# Papra_v0_5.net
KiCad netlist of a schematic drawn in EAGLE
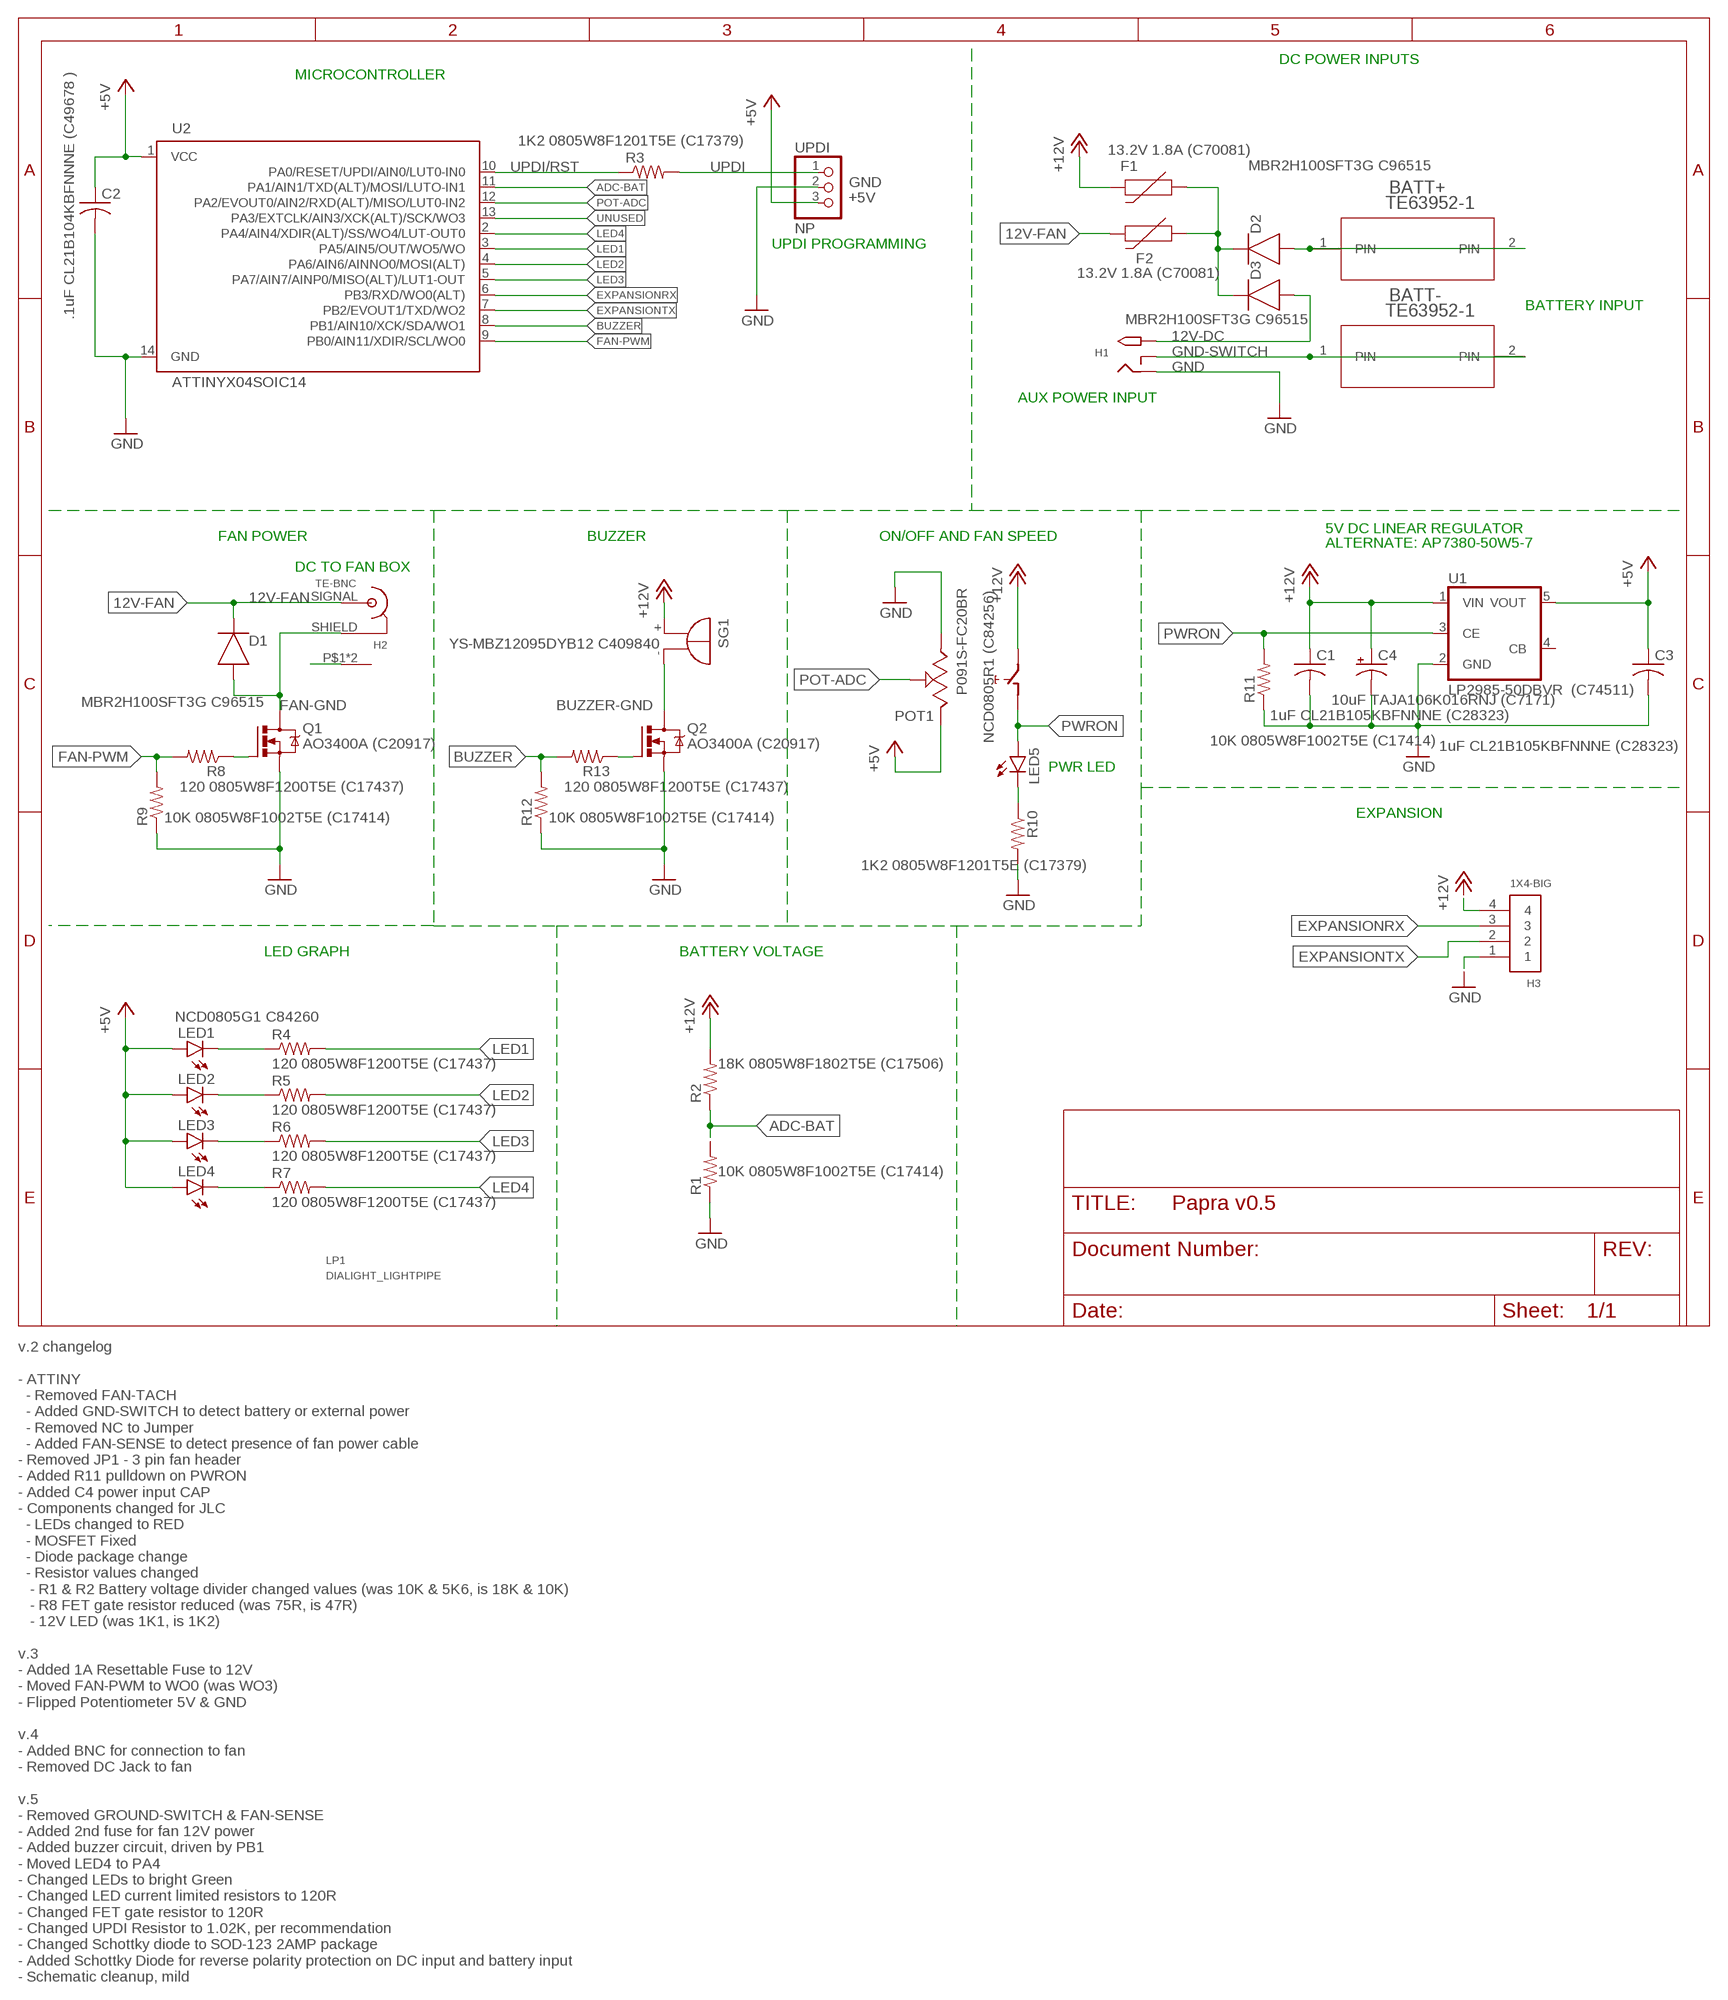
[diagram p0: schematic, sheet 1]

(export (version "E")
  (design (tool "Eeschema 10.0.6"))
  (components
    (comp (ref "BATT+")
      (value "TE63952-1")
      (footprint "eagle-import:TE63952-1")
      (libsource (lib "eagle-import") (part "TE63952-1"))
    )
    (comp (ref "BATT-")
      (value "TE63952-1")
      (footprint "eagle-import:TE63952-1")
      (libsource (lib "eagle-import") (part "TE63952-1"))
    )
    (comp (ref "C1")
      (value "1uF CL21B105KBFNNNE (C28323)")
      (footprint "eagle-import:C0805")
      (libsource (lib "eagle-import") (part "C-USC0805"))
    )
    (comp (ref "C2")
      (value ".1uF CL21B104KBFNNNE (C49678 )")
      (footprint "eagle-import:C0805")
      (libsource (lib "eagle-import") (part "C-USC0805"))
    )
    (comp (ref "C3")
      (value "1uF CL21B105KBFNNNE (C28323)")
      (footprint "eagle-import:C0805")
      (libsource (lib "eagle-import") (part "C-USC0805"))
    )
    (comp (ref "C4")
      (value "10uF TAJA106K016RNJ (C7171)")
      (footprint "eagle-import:A_3216-18R")
      (libsource (lib "eagle-import") (part "CPOL-USA/3216-18R"))
    )
    (comp (ref "D1")
      (value "MBR2H100SFT3G C96515")
      (footprint "eagle-import:SODFL3718X115")
      (libsource (lib "eagle-import") (part "DIODEDO-219-AB(SOD123F)_"))
    )
    (comp (ref "D2")
      (value "MBR2H100SFT3G C96515")
      (footprint "eagle-import:SODFL3718X115")
      (libsource (lib "eagle-import") (part "DIODEDO-219-AB(SOD123F)_"))
    )
    (comp (ref "D3")
      (value "MBR2H100SFT3G C96515")
      (footprint "eagle-import:SODFL3718X115")
      (libsource (lib "eagle-import") (part "DIODEDO-219-AB(SOD123F)_"))
    )
    (comp (ref "F1")
      (value "13.2V 1.8A (C70081)")
      (footprint "eagle-import:1206")
      (libsource (lib "eagle-import") (part "PPTC_HALF-AMP"))
    )
    (comp (ref "F2")
      (value "13.2V 1.8A (C70081)")
      (footprint "eagle-import:1206")
      (libsource (lib "eagle-import") (part "PPTC_HALF-AMP"))
    )
    (comp (ref "H1")
      (value "M-CUI-PJ-066A")
      (footprint "eagle-import:DCJACK-PJ-066A")
      (libsource (lib "eagle-import") (part "PJ-066A"))
    )
    (comp (ref "H2")
      (value "TE-BNC")
      (footprint "eagle-import:TE-BNC")
      (libsource (lib "eagle-import") (part "TE-BNC"))
    )
    (comp (ref "H3")
      (value "1X4-BIG")
      (footprint "eagle-import:1X04-BIG")
      (libsource (lib "eagle-import") (part "1X4-BIG"))
    )
    (comp (ref "LED1")
      (value "NCD0805G1 C84260")
      (footprint "eagle-import:CHIPLED_0805")
      (libsource (lib "eagle-import") (part "LEDCHIPLED_0805"))
    )
    (comp (ref "LED2")
      (value "NCD0805G1 C84260")
      (footprint "eagle-import:CHIPLED_0805")
      (libsource (lib "eagle-import") (part "LEDCHIPLED_0805"))
    )
    (comp (ref "LED3")
      (value "NCD0805G1 C84260")
      (footprint "eagle-import:CHIPLED_0805")
      (libsource (lib "eagle-import") (part "LEDCHIPLED_0805"))
    )
    (comp (ref "LED4")
      (value "NCD0805G1 C84260")
      (footprint "eagle-import:CHIPLED_0805")
      (libsource (lib "eagle-import") (part "LEDCHIPLED_0805"))
    )
    (comp (ref "LED5")
      (value "NCD0805R1 (C84256)")
      (footprint "eagle-import:CHIPLED_0805")
      (libsource (lib "eagle-import") (part "LEDCHIPLED_0805"))
    )
    (comp (ref "LP1")
      (value "DIALIGHT_LIGHTPIPE")
      (footprint "eagle-import:DIALIGHT_5151020F__LEDS")
      (libsource (lib "eagle-import") (part "DIALIGHT_LIGHTPIPE"))
    )
    (comp (ref "POT1")
      (value "P091S-FC20BR")
      (footprint "eagle-import:P091S-FC20BR")
      (libsource (lib "eagle-import") (part "P091S-FC20BR"))
    )
    (comp (ref "Q1")
      (value "AO3400A (C20917)")
      (footprint "eagle-import:SOT23")
      (fields (field (name "MANUFACTURER") "ON Semiconductor") (field (name "MPN") "BSS123L"))
      (libsource (lib "eagle-import") (part "NMOSFET_-SOT23BSS123"))
    )
    (comp (ref "Q2")
      (value "AO3400A (C20917)")
      (footprint "eagle-import:SOT23")
      (fields (field (name "MANUFACTURER") "ON Semiconductor") (field (name "MPN") "BSS123L"))
      (libsource (lib "eagle-import") (part "NMOSFET_-SOT23BSS123"))
    )
    (comp (ref "R1")
      (value "10K 0805W8F1002T5E (C17414)")
      (footprint "eagle-import:R0805")
      (libsource (lib "eagle-import") (part "R-US_R0805"))
    )
    (comp (ref "R2")
      (value "18K 0805W8F1802T5E (C17506)")
      (footprint "eagle-import:R0805")
      (libsource (lib "eagle-import") (part "R-US_R0805"))
    )
    (comp (ref "R3")
      (value "1K2 0805W8F1201T5E (C17379)")
      (footprint "eagle-import:R0805")
      (libsource (lib "eagle-import") (part "R-US_R0805"))
    )
    (comp (ref "R4")
      (value "120 0805W8F1200T5E (C17437)")
      (footprint "eagle-import:R0805")
      (libsource (lib "eagle-import") (part "R-US_R0805"))
    )
    (comp (ref "R5")
      (value "120 0805W8F1200T5E (C17437)")
      (footprint "eagle-import:R0805")
      (libsource (lib "eagle-import") (part "R-US_R0805"))
    )
    (comp (ref "R6")
      (value "120 0805W8F1200T5E (C17437)")
      (footprint "eagle-import:R0805")
      (libsource (lib "eagle-import") (part "R-US_R0805"))
    )
    (comp (ref "R7")
      (value "120 0805W8F1200T5E (C17437)")
      (footprint "eagle-import:R0805")
      (libsource (lib "eagle-import") (part "R-US_R0805"))
    )
    (comp (ref "R8")
      (value "120 0805W8F1200T5E (C17437)")
      (footprint "eagle-import:R0805")
      (libsource (lib "eagle-import") (part "R-US_R0805"))
    )
    (comp (ref "R9")
      (value "10K 0805W8F1002T5E (C17414)")
      (footprint "eagle-import:R0805")
      (libsource (lib "eagle-import") (part "R-US_R0805"))
    )
    (comp (ref "R10")
      (value "1K2 0805W8F1201T5E (C17379)")
      (footprint "eagle-import:R0805")
      (libsource (lib "eagle-import") (part "R-US_R0805"))
    )
    (comp (ref "R11")
      (value "10K 0805W8F1002T5E (C17414)")
      (footprint "eagle-import:R0805")
      (libsource (lib "eagle-import") (part "R-US_R0805"))
    )
    (comp (ref "R12")
      (value "10K 0805W8F1002T5E (C17414)")
      (footprint "eagle-import:R0805")
      (libsource (lib "eagle-import") (part "R-US_R0805"))
    )
    (comp (ref "R13")
      (value "120 0805W8F1200T5E (C17437)")
      (footprint "eagle-import:R0805")
      (libsource (lib "eagle-import") (part "R-US_R0805"))
    )
    (comp (ref "SG1")
      (value "YS-MBZ12095DYB12 C409840")
      (footprint "eagle-import:F_TMB")
      (libsource (lib "eagle-import") (part "F/TMB"))
    )
    (comp (ref "U1")
      (value "LP2985-50DBVR (C74511)")
      (footprint "eagle-import:SOT25")
      (libsource (lib "eagle-import") (part "TS520533"))
    )
    (comp (ref "U2")
      (value "ATTINYX04SOIC14")
      (footprint "eagle-import:SOIC127P600X144-14")
      (libsource (lib "eagle-import") (part "ATTINYX04SOIC14"))
    )
    (comp (ref "UPDI")
      (value "NP")
      (footprint "eagle-import:1X03")
      (libsource (lib "eagle-import") (part "PINHD-1X3"))
    )
  )
  (nets
    (net (code "1") (name "+5V") (class "Default")
      (node (ref "C2") (pin "1") (pinfunction "1_1") (pintype "passive"))
      (node (ref "C3") (pin "1") (pinfunction "1_1") (pintype "passive"))
      (node (ref "LED1") (pin "A") (pinfunction "A_A") (pintype "passive"))
      (node (ref "LED2") (pin "A") (pinfunction "A_A") (pintype "passive"))
      (node (ref "LED3") (pin "A") (pinfunction "A_A") (pintype "passive"))
      (node (ref "LED4") (pin "A") (pinfunction "A_A") (pintype "passive"))
      (node (ref "POT1") (pin "3") (pinfunction "3_3") (pintype "passive"))
      (node (ref "U1") (pin "5") (pinfunction "VOUT_5") (pintype "passive"))
      (node (ref "U2") (pin "1") (pinfunction "VCC_1") (pintype "power_in"))
      (node (ref "UPDI") (pin "3") (pinfunction "3_3") (pintype "passive"))
    )
    (net (code "2") (name "+12V") (class "Default")
      (node (ref "C1") (pin "1") (pinfunction "1_1") (pintype "passive"))
      (node (ref "C4") (pin "+") (pinfunction "+_+") (pintype "passive"))
      (node (ref "F1") (pin "2") (pinfunction "2_2") (pintype "bidirectional"))
      (node (ref "H3") (pin "4") (pinfunction "4_4") (pintype "bidirectional"))
      (node (ref "POT1") (pin "NO") (pinfunction "5_NO") (pintype "passive"))
      (node (ref "R2") (pin "2") (pinfunction "2_2") (pintype "passive"))
      (node (ref "SG1") (pin "+") (pinfunction "+_+") (pintype "passive"))
      (node (ref "U1") (pin "1") (pinfunction "VIN_1") (pintype "input"))
    )
    (net (code "3") (name "/12V-DC") (class "Default")
      (node (ref "D3") (pin "2") (pinfunction "A_2") (pintype "passive"))
      (node (ref "H1") (pin "PWR") (pinfunction "TIP_PWR") (pintype "bidirectional"))
    )
    (net (code "4") (name "/BUZZER-GND") (class "Default")
      (node (ref "Q2") (pin "3") (pinfunction "D_3") (pintype "passive"))
      (node (ref "SG1") (pin "-") (pinfunction "-_-") (pintype "passive"))
    )
    (net (code "5") (name "/FAN-GND") (class "Default")
      (node (ref "D1") (pin "2") (pinfunction "A_2") (pintype "passive"))
      (node (ref "H2") (pin "SHIELD") (pinfunction "P2_SHIELD") (pintype "passive"))
      (node (ref "Q1") (pin "3") (pinfunction "D_3") (pintype "passive"))
    )
    (net (code "6") (name "/GND-SWITCH") (class "Default")
      (node (ref "BATT-") (pin "1") (pinfunction "PIN_1") (pintype "passive"))
      (node (ref "BATT-") (pin "2") (pinfunction "PIN_2") (pintype "passive"))
      (node (ref "H1") (pin "GNDBREAK") (pinfunction "RING_SW_GNDBREAK") (pintype "bidirectional"))
    )
    (net (code "7") (name "/UPDI") (class "Default")
      (node (ref "R3") (pin "2") (pinfunction "2_2") (pintype "passive"))
      (node (ref "UPDI") (pin "1") (pinfunction "1_1") (pintype "passive"))
    )
    (net (code "8") (name "/UPDI{slash}RST") (class "Default")
      (node (ref "R3") (pin "1") (pinfunction "1_1") (pintype "passive"))
      (node (ref "U2") (pin "10") (pinfunction "PA0/RESET/UPDI/AIN0/LUT0-IN0_10") (pintype "bidirectional"))
    )
    (net (code "9") (name "12V-FAN") (class "Default")
      (node (ref "D1") (pin "1") (pinfunction "C_1") (pintype "passive"))
      (node (ref "F2") (pin "2") (pinfunction "2_2") (pintype "bidirectional"))
      (node (ref "H2") (pin "SIGNAL") (pinfunction "P1_SIGNAL") (pintype "passive"))
    )
    (net (code "10") (name "ADC-BAT") (class "Default")
      (node (ref "R1") (pin "2") (pinfunction "2_2") (pintype "passive"))
      (node (ref "R2") (pin "1") (pinfunction "1_1") (pintype "passive"))
      (node (ref "U2") (pin "11") (pinfunction "PA1/AIN1/TXD(ALT)/MOSI/LUTO-IN1_11") (pintype "bidirectional"))
    )
    (net (code "11") (name "BUZZER") (class "Default")
      (node (ref "R12") (pin "2") (pinfunction "2_2") (pintype "passive"))
      (node (ref "R13") (pin "2") (pinfunction "2_2") (pintype "passive"))
      (node (ref "U2") (pin "8") (pinfunction "PB1/AIN10/XCK/SDA/WO1_8") (pintype "bidirectional"))
    )
    (net (code "12") (name "EXPANSIONRX") (class "Default")
      (node (ref "H3") (pin "3") (pinfunction "3_3") (pintype "bidirectional"))
      (node (ref "U2") (pin "6") (pinfunction "PB3/RXD/WO0(ALT)_6") (pintype "bidirectional"))
    )
    (net (code "13") (name "EXPANSIONTX") (class "Default")
      (node (ref "H3") (pin "2") (pinfunction "2_2") (pintype "bidirectional"))
      (node (ref "U2") (pin "7") (pinfunction "PB2/EVOUT1/TXD/WO2_7") (pintype "bidirectional"))
    )
    (net (code "14") (name "FAN-PWM") (class "Default")
      (node (ref "R8") (pin "2") (pinfunction "2_2") (pintype "passive"))
      (node (ref "R9") (pin "2") (pinfunction "2_2") (pintype "passive"))
      (node (ref "U2") (pin "9") (pinfunction "PB0/AIN11/XDIR/SCL/WO0_9") (pintype "bidirectional"))
    )
    (net (code "15") (name "GND") (class "Default")
      (node (ref "C1") (pin "2") (pinfunction "2_2") (pintype "passive"))
      (node (ref "C2") (pin "2") (pinfunction "2_2") (pintype "passive"))
      (node (ref "C3") (pin "2") (pinfunction "2_2") (pintype "passive"))
      (node (ref "C4") (pin "-") (pinfunction "-_-") (pintype "passive"))
      (node (ref "H1") (pin "GND") (pinfunction "RING_GND") (pintype "bidirectional"))
      (node (ref "H3") (pin "1") (pinfunction "1_1") (pintype "bidirectional"))
      (node (ref "POT1") (pin "1") (pinfunction "1_1") (pintype "passive"))
      (node (ref "Q1") (pin "2") (pinfunction "S_2") (pintype "passive"))
      (node (ref "Q2") (pin "2") (pinfunction "S_2") (pintype "passive"))
      (node (ref "R1") (pin "1") (pinfunction "1_1") (pintype "passive"))
      (node (ref "R10") (pin "2") (pinfunction "2_2") (pintype "passive"))
      (node (ref "R11") (pin "1") (pinfunction "1_1") (pintype "passive"))
      (node (ref "R12") (pin "1") (pinfunction "1_1") (pintype "passive"))
      (node (ref "R9") (pin "1") (pinfunction "1_1") (pintype "passive"))
      (node (ref "U1") (pin "2") (pinfunction "GND_2") (pintype "passive"))
      (node (ref "U2") (pin "14") (pinfunction "GND_14") (pintype "power_in"))
      (node (ref "UPDI") (pin "2") (pinfunction "2_2") (pintype "passive"))
    )
    (net (code "16") (name "LED1") (class "Default")
      (node (ref "R4") (pin "2") (pinfunction "2_2") (pintype "passive"))
      (node (ref "U2") (pin "3") (pinfunction "PA5/AIN5/OUT/WO5/WO_3") (pintype "bidirectional"))
    )
    (net (code "17") (name "LED2") (class "Default")
      (node (ref "R5") (pin "2") (pinfunction "2_2") (pintype "passive"))
      (node (ref "U2") (pin "4") (pinfunction "PA6/AIN6/AINNO0/MOSI(ALT)_4") (pintype "bidirectional"))
    )
    (net (code "18") (name "LED3") (class "Default")
      (node (ref "R6") (pin "2") (pinfunction "2_2") (pintype "passive"))
      (node (ref "U2") (pin "5") (pinfunction "PA7/AIN7/AINP0/MISO(ALT)/LUT1-OUT_5") (pintype "bidirectional"))
    )
    (net (code "19") (name "LED4") (class "Default")
      (node (ref "R7") (pin "2") (pinfunction "2_2") (pintype "passive"))
      (node (ref "U2") (pin "2") (pinfunction "PA4/AIN4/XDIR(ALT)/SS/WO4/LUT-OUT0_2") (pintype "bidirectional"))
    )
    (net (code "20") (name "Net-(D2-A)") (class "Default")
      (node (ref "BATT+") (pin "1") (pinfunction "PIN_1") (pintype "passive"))
      (node (ref "BATT+") (pin "2") (pinfunction "PIN_2") (pintype "passive"))
      (node (ref "D2") (pin "2") (pinfunction "A_2") (pintype "passive"))
    )
    (net (code "21") (name "Net-(D2-C)") (class "Default")
      (node (ref "D2") (pin "1") (pinfunction "C_1") (pintype "passive"))
      (node (ref "D3") (pin "1") (pinfunction "C_1") (pintype "passive"))
      (node (ref "F1") (pin "1") (pinfunction "1_1") (pintype "bidirectional"))
      (node (ref "F2") (pin "1") (pinfunction "1_1") (pintype "bidirectional"))
    )
    (net (code "22") (name "Net-(H2-P3-PadP$1)") (class "Default")
      (node (ref "H2") (pin "P$1") (pinfunction "P3_P$1") (pintype "passive"))
      (node (ref "H2") (pin "P$2") (pinfunction "P3_P$2") (pintype "passive"))
    )
    (net (code "23") (name "Net-(LED1-PadC)") (class "Default")
      (node (ref "LED1") (pin "C") (pinfunction "C_C") (pintype "passive"))
      (node (ref "R4") (pin "1") (pinfunction "1_1") (pintype "passive"))
    )
    (net (code "24") (name "Net-(LED2-PadC)") (class "Default")
      (node (ref "LED2") (pin "C") (pinfunction "C_C") (pintype "passive"))
      (node (ref "R5") (pin "1") (pinfunction "1_1") (pintype "passive"))
    )
    (net (code "25") (name "Net-(LED3-PadC)") (class "Default")
      (node (ref "LED3") (pin "C") (pinfunction "C_C") (pintype "passive"))
      (node (ref "R6") (pin "1") (pinfunction "1_1") (pintype "passive"))
    )
    (net (code "26") (name "Net-(LED4-PadC)") (class "Default")
      (node (ref "LED4") (pin "C") (pinfunction "C_C") (pintype "passive"))
      (node (ref "R7") (pin "1") (pinfunction "1_1") (pintype "passive"))
    )
    (net (code "27") (name "Net-(LED5-PadC)") (class "Default")
      (node (ref "LED5") (pin "C") (pinfunction "C_C") (pintype "passive"))
      (node (ref "R10") (pin "1") (pinfunction "1_1") (pintype "passive"))
    )
    (net (code "28") (name "Net-(Q1-G)") (class "Default")
      (node (ref "Q1") (pin "1") (pinfunction "G_1") (pintype "passive"))
      (node (ref "R8") (pin "1") (pinfunction "1_1") (pintype "passive"))
    )
    (net (code "29") (name "Net-(Q2-G)") (class "Default")
      (node (ref "Q2") (pin "1") (pinfunction "G_1") (pintype "passive"))
      (node (ref "R13") (pin "1") (pinfunction "1_1") (pintype "passive"))
    )
    (net (code "30") (name "POT-ADC") (class "Default")
      (node (ref "POT1") (pin "2") (pinfunction "2_2") (pintype "passive"))
      (node (ref "U2") (pin "12") (pinfunction "PA2/EVOUT0/AIN2/RXD(ALT)/MISO/LUT0-IN2_12") (pintype "bidirectional"))
    )
    (net (code "31") (name "PWRON") (class "Default")
      (node (ref "LED5") (pin "A") (pinfunction "A_A") (pintype "passive"))
      (node (ref "POT1") (pin "COM") (pinfunction "4_COM") (pintype "passive"))
      (node (ref "R11") (pin "2") (pinfunction "2_2") (pintype "passive"))
      (node (ref "U1") (pin "3") (pinfunction "CE_3") (pintype "input"))
    )
    (net (code "32") (name "UNUSED") (class "Default")
      (node (ref "U2") (pin "13") (pinfunction "PA3/EXTCLK/AIN3/XCK(ALT)/SCK/WO3_13") (pintype "bidirectional"))
    )
    (net (code "33") (name "unconnected-(U1-CB-Pad4)") (class "Default")
      (node (ref "U1") (pin "4") (pinfunction "CB_4") (pintype "input"))
    )
  )
)
